# Dogfish3D_-_MCU_-_ATSAMD21G18.net
KiCad netlist of a schematic drawn in Altium Designer
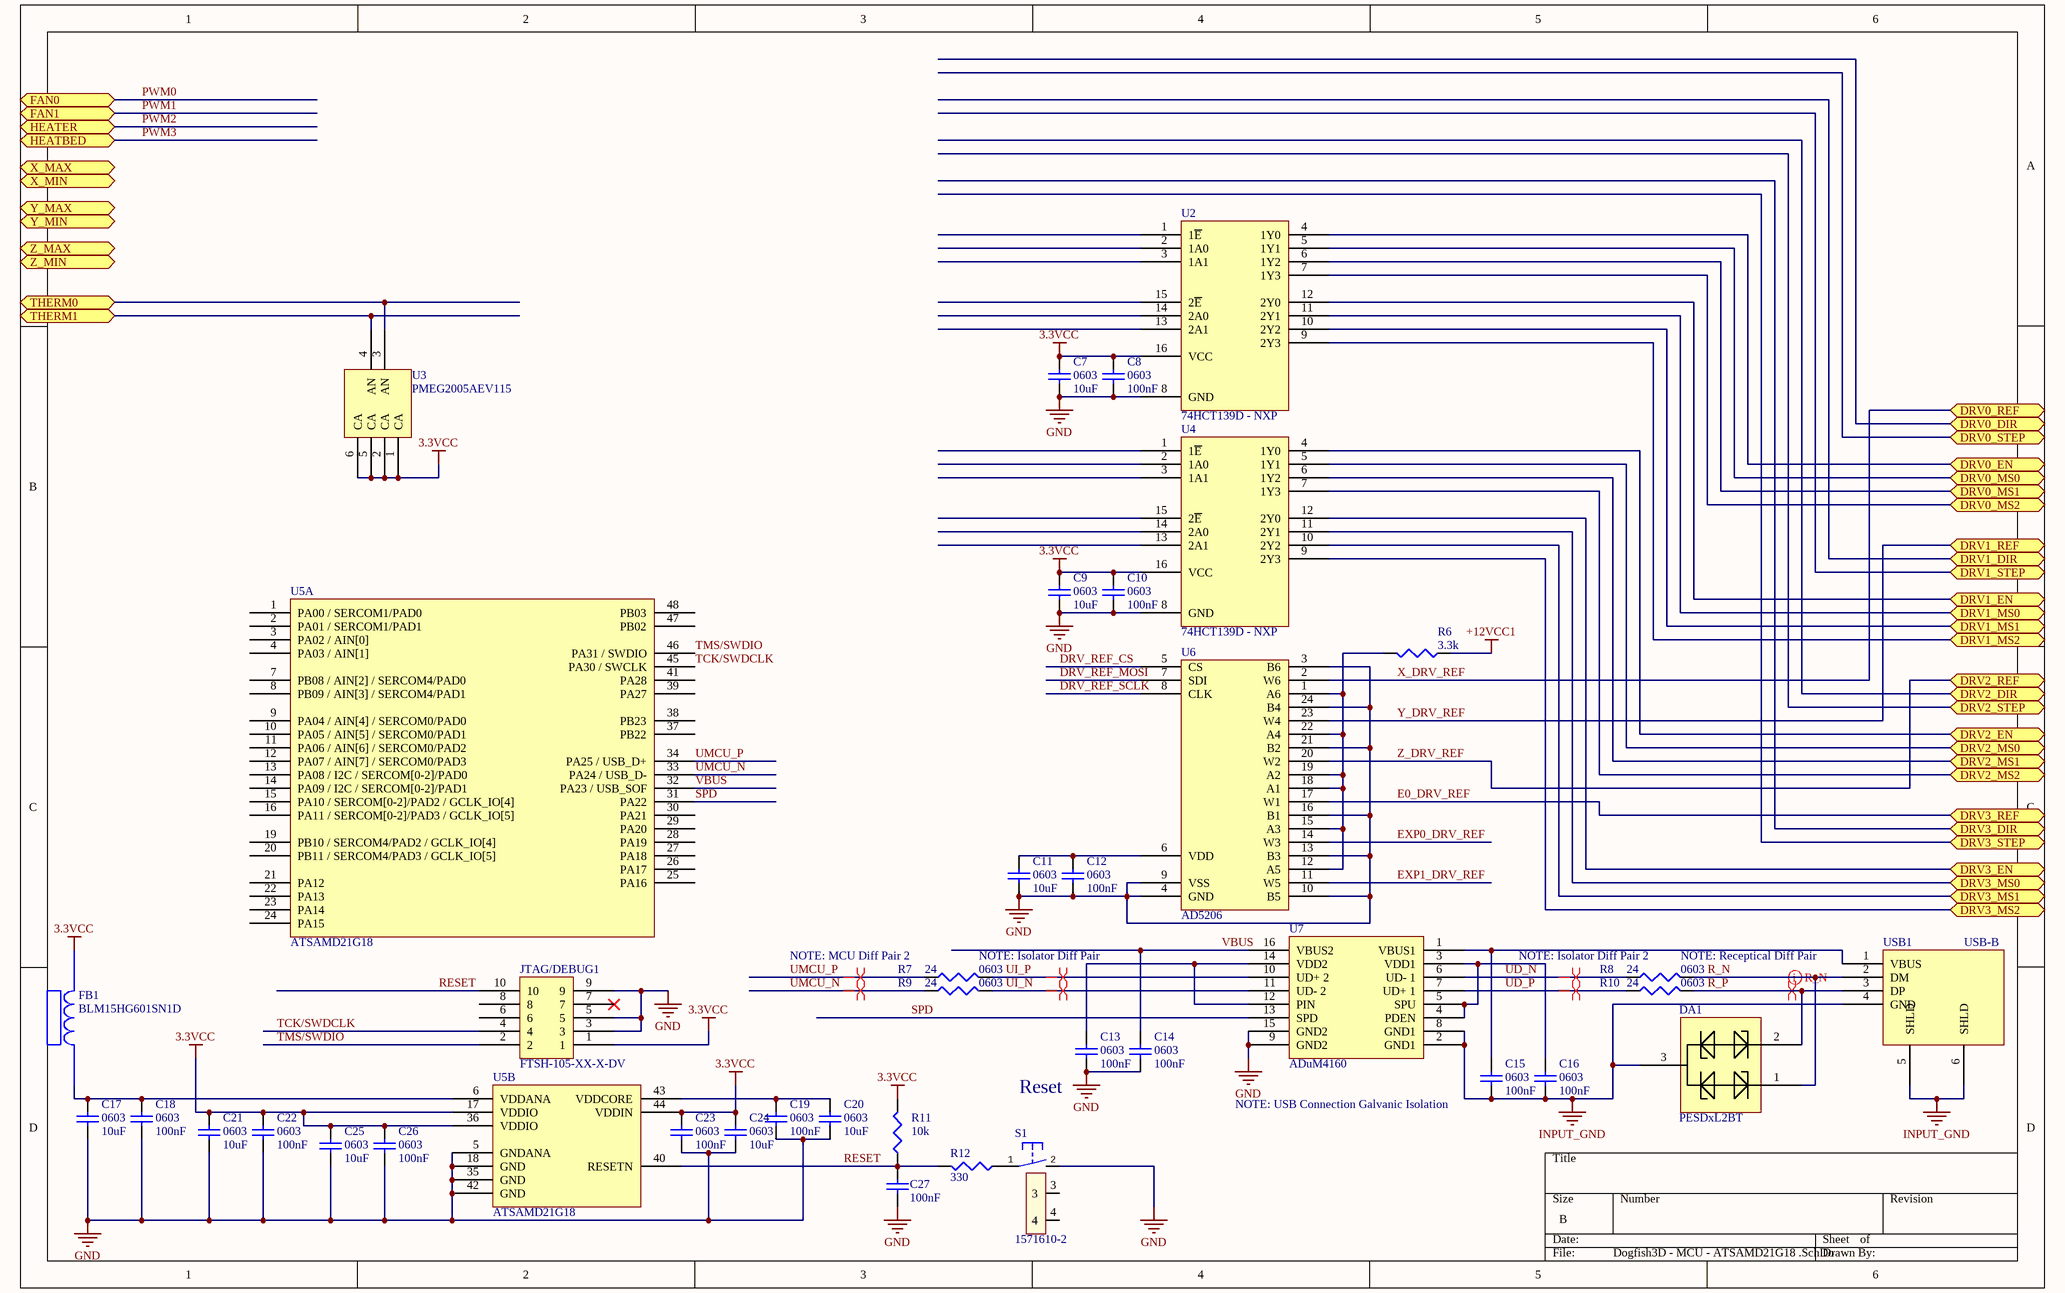
[diagram p0: Dogfish3D - MCU - ATSAMD21G18 .SchDoc]

(export (version "E")
  (design (tool "Eeschema 10.0.6"))
  (components
    (comp (ref "C7")
      (value "0603")
      (footprint "1608[0603]")
      (description "Capacitor (Semiconductor SIM Model)")
      (fields (field (name "ALTIUM_VALUE") "10uF") (field (name "PUBLISHER") "Altium Limited"))
      (libsource (lib "Miscellaneous Devices") (part "Cap Semi"))
    )
    (comp (ref "C8")
      (value "0603")
      (footprint "1608[0603]")
      (description "Capacitor (Semiconductor SIM Model)")
      (fields (field (name "ALTIUM_VALUE") "100nF") (field (name "PUBLISHER") "Altium Limited"))
      (libsource (lib "Miscellaneous Devices") (part "Cap Semi"))
    )
    (comp (ref "C9")
      (value "0603")
      (footprint "1608[0603]")
      (description "Capacitor (Semiconductor SIM Model)")
      (fields (field (name "ALTIUM_VALUE") "10uF") (field (name "PUBLISHER") "Altium Limited"))
      (libsource (lib "Miscellaneous Devices") (part "Cap Semi"))
    )
    (comp (ref "C10")
      (value "0603")
      (footprint "1608[0603]")
      (description "Capacitor (Semiconductor SIM Model)")
      (fields (field (name "ALTIUM_VALUE") "100nF") (field (name "PUBLISHER") "Altium Limited"))
      (libsource (lib "Miscellaneous Devices") (part "Cap Semi"))
    )
    (comp (ref "C11")
      (value "0603")
      (footprint "1608[0603]")
      (description "Capacitor (Semiconductor SIM Model)")
      (fields (field (name "ALTIUM_VALUE") "10uF") (field (name "PUBLISHER") "Altium Limited"))
      (libsource (lib "Miscellaneous Devices") (part "Cap Semi"))
    )
    (comp (ref "C12")
      (value "0603")
      (footprint "1608[0603]")
      (description "Capacitor (Semiconductor SIM Model)")
      (fields (field (name "ALTIUM_VALUE") "100nF") (field (name "PUBLISHER") "Altium Limited"))
      (libsource (lib "Miscellaneous Devices") (part "Cap Semi"))
    )
    (comp (ref "C13")
      (value "0603")
      (footprint "1608[0603]")
      (description "Capacitor (Semiconductor SIM Model)")
      (fields (field (name "ALTIUM_VALUE") "100nF") (field (name "PUBLISHER") "Altium Limited"))
      (libsource (lib "Miscellaneous Devices") (part "Cap Semi"))
    )
    (comp (ref "C14")
      (value "0603")
      (footprint "1608[0603]")
      (description "Capacitor (Semiconductor SIM Model)")
      (fields (field (name "ALTIUM_VALUE") "100nF") (field (name "PUBLISHER") "Altium Limited"))
      (libsource (lib "Miscellaneous Devices") (part "Cap Semi"))
    )
    (comp (ref "C15")
      (value "0603")
      (footprint "1608[0603]")
      (description "Capacitor (Semiconductor SIM Model)")
      (fields (field (name "ALTIUM_VALUE") "100nF") (field (name "PUBLISHER") "Altium Limited"))
      (libsource (lib "Miscellaneous Devices") (part "Cap Semi"))
    )
    (comp (ref "C16")
      (value "0603")
      (footprint "1608[0603]")
      (description "Capacitor (Semiconductor SIM Model)")
      (fields (field (name "ALTIUM_VALUE") "100nF") (field (name "PUBLISHER") "Altium Limited"))
      (libsource (lib "Miscellaneous Devices") (part "Cap Semi"))
    )
    (comp (ref "C17")
      (value "0603")
      (footprint "1608[0603]")
      (description "Capacitor (Semiconductor SIM Model)")
      (fields (field (name "ALTIUM_VALUE") "10uF") (field (name "PUBLISHER") "Altium Limited"))
      (libsource (lib "Miscellaneous Devices") (part "Cap Semi"))
    )
    (comp (ref "C18")
      (value "0603")
      (footprint "1608[0603]")
      (description "Capacitor (Semiconductor SIM Model)")
      (fields (field (name "ALTIUM_VALUE") "100nF") (field (name "PUBLISHER") "Altium Limited"))
      (libsource (lib "Miscellaneous Devices") (part "Cap Semi"))
    )
    (comp (ref "C19")
      (value "0603")
      (footprint "1608[0603]")
      (description "Capacitor (Semiconductor SIM Model)")
      (fields (field (name "ALTIUM_VALUE") "100nF") (field (name "PUBLISHER") "Altium Limited"))
      (libsource (lib "Miscellaneous Devices") (part "Cap Semi"))
    )
    (comp (ref "C20")
      (value "0603")
      (footprint "1608[0603]")
      (description "Capacitor (Semiconductor SIM Model)")
      (fields (field (name "ALTIUM_VALUE") "10uF") (field (name "PUBLISHER") "Altium Limited"))
      (libsource (lib "Miscellaneous Devices") (part "Cap Semi"))
    )
    (comp (ref "C21")
      (value "0603")
      (footprint "1608[0603]")
      (description "Capacitor (Semiconductor SIM Model)")
      (fields (field (name "ALTIUM_VALUE") "10uF") (field (name "PUBLISHER") "Altium Limited"))
      (libsource (lib "Miscellaneous Devices") (part "Cap Semi"))
    )
    (comp (ref "C22")
      (value "0603")
      (footprint "1608[0603]")
      (description "Capacitor (Semiconductor SIM Model)")
      (fields (field (name "ALTIUM_VALUE") "100nF") (field (name "PUBLISHER") "Altium Limited"))
      (libsource (lib "Miscellaneous Devices") (part "Cap Semi"))
    )
    (comp (ref "C23")
      (value "0603")
      (footprint "1608[0603]")
      (description "Capacitor (Semiconductor SIM Model)")
      (fields (field (name "ALTIUM_VALUE") "100nF") (field (name "PUBLISHER") "Altium Limited"))
      (libsource (lib "Miscellaneous Devices") (part "Cap Semi"))
    )
    (comp (ref "C24")
      (value "0603")
      (footprint "1608[0603]")
      (description "Capacitor (Semiconductor SIM Model)")
      (fields (field (name "ALTIUM_VALUE") "10uF") (field (name "PUBLISHER") "Altium Limited"))
      (libsource (lib "Miscellaneous Devices") (part "Cap Semi"))
    )
    (comp (ref "C25")
      (value "0603")
      (footprint "1608[0603]")
      (description "Capacitor (Semiconductor SIM Model)")
      (fields (field (name "ALTIUM_VALUE") "10uF") (field (name "PUBLISHER") "Altium Limited"))
      (libsource (lib "Miscellaneous Devices") (part "Cap Semi"))
    )
    (comp (ref "C26")
      (value "0603")
      (footprint "1608[0603]")
      (description "Capacitor (Semiconductor SIM Model)")
      (fields (field (name "ALTIUM_VALUE") "100nF") (field (name "PUBLISHER") "Altium Limited"))
      (libsource (lib "Miscellaneous Devices") (part "Cap Semi"))
    )
    (comp (ref "C27")
      (value "100nF")
      (footprint "1608[0603]")
      (description "Capacitor (Semiconductor SIM Model)")
      (fields (field (name "Comment") "Cap Semi") (field (name "PUBLISHER") "Altium Limited"))
      (libsource (lib "Miscellaneous Devices") (part "Cap Semi"))
    )
    (comp (ref "DA1")
      (value "PESDxL2BT")
      (footprint "SOT95P230X110-3N")
      (description "PESDxL2BT TVS Diode Array 2x")
      (libsource (lib "ZMBo Schematic Library") (part "PESDxL2BT"))
    )
    (comp (ref "FB1")
      (value "BLM15HG601SN1D")
      (footprint "BLM18PG121SN1D")
      (libsource (lib "AHD Part Library") (part "BLM15HG601SN1D"))
    )
    (comp (ref "JTAG/DEBUG1")
      (value "FTSH-105-XX-X-DV")
      (footprint "FTSH-105-XX-X-DV")
      (libsource (lib "Adams Altium Library") (part "ARM Cortex JTAG-DEBUG Header"))
    )
    (comp (ref "R6")
      (value "3.3k")
      (footprint "J1-0603")
      (description "Resistor")
      (fields (field (name "Comment") "Res3") (field (name "PUBLISHER") "Altium Limited"))
      (libsource (lib "Miscellaneous Devices") (part "Res3"))
    )
    (comp (ref "R7")
      (value "0603")
      (footprint "J1-0603")
      (description "Resistor")
      (fields (field (name "ALTIUM_VALUE") "24") (field (name "PUBLISHER") "Altium Limited"))
      (libsource (lib "Miscellaneous Devices") (part "Res3"))
    )
    (comp (ref "R8")
      (value "0603")
      (footprint "J1-0603")
      (description "Resistor")
      (fields (field (name "ALTIUM_VALUE") "24") (field (name "PUBLISHER") "Altium Limited"))
      (libsource (lib "Miscellaneous Devices") (part "Res3"))
    )
    (comp (ref "R9")
      (value "0603")
      (footprint "J1-0603")
      (description "Resistor")
      (fields (field (name "ALTIUM_VALUE") "24") (field (name "PUBLISHER") "Altium Limited"))
      (libsource (lib "Miscellaneous Devices") (part "Res3"))
    )
    (comp (ref "R10")
      (value "0603")
      (footprint "J1-0603")
      (description "Resistor")
      (fields (field (name "ALTIUM_VALUE") "24") (field (name "PUBLISHER") "Altium Limited"))
      (libsource (lib "Miscellaneous Devices") (part "Res3"))
    )
    (comp (ref "R11")
      (value "10k")
      (footprint "J1-0603")
      (description "Resistor")
      (fields (field (name "Comment") "Res3") (field (name "PUBLISHER") "Altium Limited"))
      (libsource (lib "Miscellaneous Devices") (part "Res3"))
    )
    (comp (ref "R12")
      (value "330")
      (footprint "J1-0603")
      (description "Resistor")
      (fields (field (name "Comment") "Res3") (field (name "PUBLISHER") "Altium Limited"))
      (libsource (lib "Miscellaneous Devices") (part "Res3"))
    )
    (comp (ref "S1")
      (value "1571610-2")
      (footprint "B3F-31XX")
      (description "SWTCH Momentary Washable")
      (fields
        (field (name "MANUFACTURER") "Omron")
        (field (name "MANUFACTURER_1") "TE")
        (field (name "PUBLISHER") "UltiMachine")
      )
      (libsource (lib "ZMBo Schematic Library") (part "1571610-2_1"))
    )
    (comp (ref "U2")
      (value "74HCT139D - NXP")
      (footprint "SOIC127P600X175-16N")
      (description "74HCT139D 2-4 dual Decoder from NXP")
      (libsource (lib "Dogfish3D") (part "74HCT139D - NXP"))
    )
    (comp (ref "U3")
      (value "PMEG2005AEV115")
      (footprint "PMEG2005AEV115")
      (libsource (lib "Adams Altium Library") (part "PMEG2005AEV115"))
    )
    (comp (ref "U4")
      (value "74HCT139D - NXP")
      (footprint "SOIC127P600X175-16N")
      (description "74HCT139D 2-4 dual Decoder from NXP")
      (libsource (lib "Dogfish3D") (part "74HCT139D - NXP"))
    )
    (comp (ref "U5")
      (value "ATSAMD21G18")
      (footprint "TSQFP50P900X900X120-48N")
      (libsource (lib "Dogfish3D") (part "ATSAMD21G18"))
    )
    (comp (ref "U6")
      (value "AD5206")
      (footprint "AD5206 & AD5204")
      (libsource (lib "ZMBo Schematic Library") (part "AD5206"))
    )
    (comp (ref "U7")
      (value "ADuM4160")
      (footprint "ADuM4160")
      (description "USB Opto Isolator")
      (libsource (lib "ZMBo Schematic Library") (part "ADuM4160"))
    )
    (comp (ref "USB1")
      (value "USB-B")
      (footprint "PN61729")
      (libsource (lib "ZMBo Schematic Library") (part "USB-B"))
    )
  )
  (nets
    (net (code "1") (name "+12VCC1") (class "Default")
      (node (ref "R6") (pin "1") (pinfunction "1_1") (pintype "passive"))
    )
    (net (code "3") (name "/DRV0_EN") (class "Default")
      (node (ref "U2") (pin "4") (pinfunction "1Y0_4") (pintype "passive"))
    )
    (net (code "4") (name "/DRV0_MS0") (class "Default")
      (node (ref "U2") (pin "5") (pinfunction "1Y1_5") (pintype "passive"))
    )
    (net (code "5") (name "/DRV0_MS1") (class "Default")
      (node (ref "U2") (pin "6") (pinfunction "1Y2_6") (pintype "passive"))
    )
    (net (code "6") (name "/DRV0_MS2") (class "Default")
      (node (ref "U2") (pin "7") (pinfunction "1Y3_7") (pintype "passive"))
    )
    (net (code "9") (name "/DRV1_EN") (class "Default")
      (node (ref "U2") (pin "12") (pinfunction "2Y0_12") (pintype "passive"))
    )
    (net (code "10") (name "/DRV1_MS0") (class "Default")
      (node (ref "U2") (pin "11") (pinfunction "2Y1_11") (pintype "passive"))
    )
    (net (code "11") (name "/DRV1_MS1") (class "Default")
      (node (ref "U2") (pin "10") (pinfunction "2Y2_10") (pintype "passive"))
    )
    (net (code "12") (name "/DRV1_MS2") (class "Default")
      (node (ref "U2") (pin "9") (pinfunction "2Y3_9") (pintype "passive"))
    )
    (net (code "15") (name "/DRV2_EN") (class "Default")
      (node (ref "U4") (pin "4") (pinfunction "1Y0_4") (pintype "passive"))
    )
    (net (code "16") (name "/DRV2_MS0") (class "Default")
      (node (ref "U4") (pin "5") (pinfunction "1Y1_5") (pintype "passive"))
    )
    (net (code "17") (name "/DRV2_MS1") (class "Default")
      (node (ref "U4") (pin "6") (pinfunction "1Y2_6") (pintype "passive"))
    )
    (net (code "18") (name "/DRV2_MS2") (class "Default")
      (node (ref "U4") (pin "7") (pinfunction "1Y3_7") (pintype "passive"))
    )
    (net (code "21") (name "/DRV3_EN") (class "Default")
      (node (ref "U4") (pin "12") (pinfunction "2Y0_12") (pintype "passive"))
    )
    (net (code "22") (name "/DRV3_MS0") (class "Default")
      (node (ref "U4") (pin "11") (pinfunction "2Y1_11") (pintype "passive"))
    )
    (net (code "23") (name "/DRV3_MS1") (class "Default")
      (node (ref "U4") (pin "10") (pinfunction "2Y2_10") (pintype "passive"))
    )
    (net (code "24") (name "/DRV3_MS2") (class "Default")
      (node (ref "U4") (pin "9") (pinfunction "2Y3_9") (pintype "passive"))
    )
    (net (code "26") (name "/DRV_REF_CS") (class "Default")
      (node (ref "U6") (pin "5") (pinfunction "CS_5") (pintype "passive"))
    )
    (net (code "27") (name "/DRV_REF_MOSI") (class "Default")
      (node (ref "U6") (pin "7") (pinfunction "SDI_7") (pintype "passive"))
    )
    (net (code "28") (name "/DRV_REF_SCLK") (class "Default")
      (node (ref "U6") (pin "8") (pinfunction "CLK_8") (pintype "passive"))
    )
    (net (code "29") (name "/E0_DRV_REF") (class "Default")
      (node (ref "U6") (pin "17") (pinfunction "W1_17") (pintype "passive"))
    )
    (net (code "30") (name "/EXP0_DRV_REF") (class "Default")
      (node (ref "U6") (pin "14") (pinfunction "W3_14") (pintype "passive"))
    )
    (net (code "31") (name "/EXP1_DRV_REF") (class "Default")
      (node (ref "U6") (pin "11") (pinfunction "W5_11") (pintype "passive"))
    )
    (net (code "36") (name "/RESET") (class "Default")
      (node (ref "C27") (pin "2") (pinfunction "2_2") (pintype "passive"))
      (node (ref "JTAG/DEBUG1") (pin "10") (pinfunction "10_10") (pintype "passive"))
      (node (ref "R11") (pin "1") (pinfunction "1_1") (pintype "passive"))
      (node (ref "R12") (pin "2") (pinfunction "2_2") (pintype "passive"))
      (node (ref "U5") (pin "40") (pinfunction "RESETN_40") (pintype "passive"))
    )
    (net (code "37") (name "/R_N") (class "Default")
      (node (ref "DA1") (pin "1") (pinfunction "1_1") (pintype "passive"))
      (node (ref "R8") (pin "2") (pinfunction "2_2") (pintype "passive"))
      (node (ref "USB1") (pin "2") (pinfunction "DM_2") (pintype "passive"))
    )
    (net (code "38") (name "/R_P") (class "Default")
      (node (ref "DA1") (pin "2") (pinfunction "2_2") (pintype "passive"))
      (node (ref "R10") (pin "2") (pinfunction "2_2") (pintype "passive"))
      (node (ref "USB1") (pin "3") (pinfunction "DP_3") (pintype "passive"))
    )
    (net (code "39") (name "/SPD") (class "Default")
      (node (ref "U5") (pin "31") (pinfunction "PA22_31") (pintype "passive"))
      (node (ref "U7") (pin "13") (pinfunction "SPD_13") (pintype "passive"))
    )
    (net (code "40") (name "/TCK{slash}SWDCLK") (class "Default")
      (node (ref "JTAG/DEBUG1") (pin "4") (pinfunction "4_4") (pintype "passive"))
      (node (ref "U5") (pin "45") (pinfunction "PA30_/_SWCLK_45") (pintype "passive"))
    )
    (net (code "41") (name "/THERM0") (class "Default")
      (node (ref "U3") (pin "3") (pinfunction "AN_3") (pintype "passive"))
    )
    (net (code "42") (name "/THERM1") (class "Default")
      (node (ref "U3") (pin "4") (pinfunction "AN_4") (pintype "passive"))
    )
    (net (code "43") (name "/TMS{slash}SWDIO") (class "Default")
      (node (ref "JTAG/DEBUG1") (pin "2") (pinfunction "2_2") (pintype "passive"))
      (node (ref "U5") (pin "46") (pinfunction "PA31_/_SWDIO_46") (pintype "passive"))
    )
    (net (code "44") (name "/UD_N") (class "Default")
      (node (ref "R8") (pin "1") (pinfunction "1_1") (pintype "passive"))
      (node (ref "U7") (pin "6") (pinfunction "UD-_1_6") (pintype "passive"))
    )
    (net (code "45") (name "/UD_P") (class "Default")
      (node (ref "R10") (pin "1") (pinfunction "1_1") (pintype "passive"))
      (node (ref "U7") (pin "7") (pinfunction "UD+_1_7") (pintype "passive"))
    )
    (net (code "46") (name "/UI_N") (class "Default")
      (node (ref "R9") (pin "2") (pinfunction "2_2") (pintype "passive"))
      (node (ref "U7") (pin "11") (pinfunction "UD-_2_11") (pintype "passive"))
    )
    (net (code "47") (name "/UI_P") (class "Default")
      (node (ref "R7") (pin "2") (pinfunction "2_2") (pintype "passive"))
      (node (ref "U7") (pin "10") (pinfunction "UD+_2_10") (pintype "passive"))
    )
    (net (code "48") (name "/UMCU_N") (class "Default")
      (node (ref "R9") (pin "1") (pinfunction "1_1") (pintype "passive"))
      (node (ref "U5") (pin "33") (pinfunction "PA24_/_USB_D-_33") (pintype "passive"))
    )
    (net (code "49") (name "/UMCU_P") (class "Default")
      (node (ref "R7") (pin "1") (pinfunction "1_1") (pintype "passive"))
      (node (ref "U5") (pin "34") (pinfunction "PA25_/_USB_D+_34") (pintype "passive"))
    )
    (net (code "50") (name "/VBUS") (class "Default")
      (node (ref "C14") (pin "2") (pinfunction "2_2") (pintype "passive"))
      (node (ref "U5") (pin "32") (pinfunction "PA23_/_USB_SOF_32") (pintype "passive"))
      (node (ref "U7") (pin "16") (pinfunction "VBUS2_16") (pintype "passive"))
    )
    (net (code "51") (name "/X_DRV_REF") (class "Default")
      (node (ref "U6") (pin "2") (pinfunction "W6_2") (pintype "passive"))
    )
    (net (code "54") (name "/Y_DRV_REF") (class "Default")
      (node (ref "U6") (pin "23") (pinfunction "W4_23") (pintype "passive"))
    )
    (net (code "57") (name "/Z_DRV_REF") (class "Default")
      (node (ref "U6") (pin "20") (pinfunction "W2_20") (pintype "passive"))
    )
    (net (code "60") (name "3.3VCC") (class "Default")
      (node (ref "C10") (pin "2") (pinfunction "2_2") (pintype "passive"))
      (node (ref "C21") (pin "2") (pinfunction "2_2") (pintype "passive"))
      (node (ref "C22") (pin "2") (pinfunction "2_2") (pintype "passive"))
      (node (ref "C23") (pin "2") (pinfunction "2_2") (pintype "passive"))
      (node (ref "C24") (pin "2") (pinfunction "2_2") (pintype "passive"))
      (node (ref "C25") (pin "2") (pinfunction "2_2") (pintype "passive"))
      (node (ref "C26") (pin "2") (pinfunction "2_2") (pintype "passive"))
      (node (ref "C7") (pin "2") (pinfunction "2_2") (pintype "passive"))
      (node (ref "C8") (pin "2") (pinfunction "2_2") (pintype "passive"))
      (node (ref "C9") (pin "2") (pinfunction "2_2") (pintype "passive"))
      (node (ref "FB1") (pin "2") (pinfunction "2_2") (pintype "passive"))
      (node (ref "JTAG/DEBUG1") (pin "1") (pinfunction "1_1") (pintype "passive"))
      (node (ref "R11") (pin "2") (pinfunction "2_2") (pintype "passive"))
      (node (ref "U2") (pin "16") (pinfunction "VCC_16") (pintype "passive"))
      (node (ref "U3") (pin "1") (pinfunction "CA_1") (pintype "passive"))
      (node (ref "U3") (pin "2") (pinfunction "CA_2") (pintype "passive"))
      (node (ref "U3") (pin "5") (pinfunction "CA_5") (pintype "passive"))
      (node (ref "U3") (pin "6") (pinfunction "CA_6") (pintype "passive"))
      (node (ref "U4") (pin "16") (pinfunction "VCC_16") (pintype "passive"))
      (node (ref "U5") (pin "17") (pinfunction "VDDIO_17") (pintype "passive"))
      (node (ref "U5") (pin "36") (pinfunction "VDDIO_36") (pintype "passive"))
      (node (ref "U5") (pin "44") (pinfunction "VDDIN_44") (pintype "passive"))
    )
    (net (code "61") (name "GND") (class "Default")
      (node (ref "C10") (pin "1") (pinfunction "1_1") (pintype "passive"))
      (node (ref "C11") (pin "1") (pinfunction "1_1") (pintype "passive"))
      (node (ref "C12") (pin "1") (pinfunction "1_1") (pintype "passive"))
      (node (ref "C13") (pin "1") (pinfunction "1_1") (pintype "passive"))
      (node (ref "C14") (pin "1") (pinfunction "1_1") (pintype "passive"))
      (node (ref "C17") (pin "1") (pinfunction "1_1") (pintype "passive"))
      (node (ref "C18") (pin "1") (pinfunction "1_1") (pintype "passive"))
      (node (ref "C19") (pin "1") (pinfunction "1_1") (pintype "passive"))
      (node (ref "C20") (pin "1") (pinfunction "1_1") (pintype "passive"))
      (node (ref "C21") (pin "1") (pinfunction "1_1") (pintype "passive"))
      (node (ref "C22") (pin "1") (pinfunction "1_1") (pintype "passive"))
      (node (ref "C23") (pin "1") (pinfunction "1_1") (pintype "passive"))
      (node (ref "C24") (pin "1") (pinfunction "1_1") (pintype "passive"))
      (node (ref "C25") (pin "1") (pinfunction "1_1") (pintype "passive"))
      (node (ref "C26") (pin "1") (pinfunction "1_1") (pintype "passive"))
      (node (ref "C27") (pin "1") (pinfunction "1_1") (pintype "passive"))
      (node (ref "C7") (pin "1") (pinfunction "1_1") (pintype "passive"))
      (node (ref "C8") (pin "1") (pinfunction "1_1") (pintype "passive"))
      (node (ref "C9") (pin "1") (pinfunction "1_1") (pintype "passive"))
      (node (ref "JTAG/DEBUG1") (pin "3") (pinfunction "3_3") (pintype "passive"))
      (node (ref "JTAG/DEBUG1") (pin "5") (pinfunction "5_5") (pintype "passive"))
      (node (ref "JTAG/DEBUG1") (pin "9") (pinfunction "9_9") (pintype "passive"))
      (node (ref "S1") (pin "2") (pinfunction "S_2") (pintype "passive"))
      (node (ref "U2") (pin "8") (pinfunction "GND_8") (pintype "passive"))
      (node (ref "U4") (pin "8") (pinfunction "GND_8") (pintype "passive"))
      (node (ref "U5") (pin "18") (pinfunction "GND_18") (pintype "passive"))
      (node (ref "U5") (pin "35") (pinfunction "GND_35") (pintype "passive"))
      (node (ref "U5") (pin "42") (pinfunction "GND_42") (pintype "passive"))
      (node (ref "U5") (pin "5") (pinfunction "GNDANA_5") (pintype "passive"))
      (node (ref "U6") (pin "10") (pinfunction "B5_10") (pintype "passive"))
      (node (ref "U6") (pin "13") (pinfunction "B3_13") (pintype "passive"))
      (node (ref "U6") (pin "16") (pinfunction "B1_16") (pintype "passive"))
      (node (ref "U6") (pin "21") (pinfunction "B2_21") (pintype "passive"))
      (node (ref "U6") (pin "24") (pinfunction "B4_24") (pintype "passive"))
      (node (ref "U6") (pin "3") (pinfunction "B6_3") (pintype "passive"))
      (node (ref "U6") (pin "4") (pinfunction "GND_4") (pintype "passive"))
      (node (ref "U6") (pin "9") (pinfunction "VSS_9") (pintype "passive"))
      (node (ref "U7") (pin "15") (pinfunction "GND2_15") (pintype "passive"))
      (node (ref "U7") (pin "9") (pinfunction "GND2_9") (pintype "passive"))
    )
    (net (code "62") (name "INPUT_GND") (class "Default")
      (node (ref "C15") (pin "1") (pinfunction "1_1") (pintype "passive"))
      (node (ref "C16") (pin "1") (pinfunction "1_1") (pintype "passive"))
      (node (ref "DA1") (pin "3") (pinfunction "3_3") (pintype "passive"))
      (node (ref "U7") (pin "2") (pinfunction "GND1_2") (pintype "passive"))
      (node (ref "U7") (pin "8") (pinfunction "GND1_8") (pintype "passive"))
      (node (ref "USB1") (pin "4") (pinfunction "GND_4") (pintype "passive"))
      (node (ref "USB1") (pin "5") (pinfunction "SHLD_5") (pintype "passive"))
      (node (ref "USB1") (pin "6") (pinfunction "SHLD_6") (pintype "passive"))
    )
    (net (code "63") (name "Net-(S1-P)") (class "Default")
      (node (ref "R12") (pin "1") (pinfunction "1_1") (pintype "passive"))
      (node (ref "S1") (pin "1") (pinfunction "P_1") (pintype "passive"))
    )
    (net (code "64") (name "Net-(U5B-VDDANA)") (class "Default")
      (node (ref "C17") (pin "2") (pinfunction "2_2") (pintype "passive"))
      (node (ref "C18") (pin "2") (pinfunction "2_2") (pintype "passive"))
      (node (ref "FB1") (pin "1") (pinfunction "1_1") (pintype "passive"))
      (node (ref "U5") (pin "6") (pinfunction "VDDANA_6") (pintype "passive"))
    )
    (net (code "65") (name "Net-(U5B-VDDCORE)") (class "Default")
      (node (ref "C19") (pin "2") (pinfunction "2_2") (pintype "passive"))
      (node (ref "C20") (pin "2") (pinfunction "2_2") (pintype "passive"))
      (node (ref "U5") (pin "43") (pinfunction "VDDCORE_43") (pintype "passive"))
    )
    (net (code "66") (name "Net-(U6-A1)") (class "Default")
      (node (ref "R6") (pin "2") (pinfunction "2_2") (pintype "passive"))
      (node (ref "U6") (pin "1") (pinfunction "A6_1") (pintype "passive"))
      (node (ref "U6") (pin "12") (pinfunction "A5_12") (pintype "passive"))
      (node (ref "U6") (pin "15") (pinfunction "A3_15") (pintype "passive"))
      (node (ref "U6") (pin "18") (pinfunction "A1_18") (pintype "passive"))
      (node (ref "U6") (pin "19") (pinfunction "A2_19") (pintype "passive"))
      (node (ref "U6") (pin "22") (pinfunction "A4_22") (pintype "passive"))
    )
    (net (code "67") (name "Net-(U6-VDD)") (class "Default")
      (node (ref "C11") (pin "2") (pinfunction "2_2") (pintype "passive"))
      (node (ref "C12") (pin "2") (pinfunction "2_2") (pintype "passive"))
      (node (ref "U6") (pin "6") (pinfunction "VDD_6") (pintype "passive"))
    )
    (net (code "68") (name "Net-(U7-PDEN)") (class "Default")
      (node (ref "C16") (pin "2") (pinfunction "2_2") (pintype "passive"))
      (node (ref "U7") (pin "3") (pinfunction "VDD1_3") (pintype "passive"))
      (node (ref "U7") (pin "4") (pinfunction "PDEN_4") (pintype "passive"))
      (node (ref "U7") (pin "5") (pinfunction "SPU_5") (pintype "passive"))
    )
    (net (code "69") (name "Net-(U7-PIN)") (class "Default")
      (node (ref "C13") (pin "2") (pinfunction "2_2") (pintype "passive"))
      (node (ref "U7") (pin "12") (pinfunction "PIN_12") (pintype "passive"))
      (node (ref "U7") (pin "14") (pinfunction "VDD2_14") (pintype "passive"))
    )
    (net (code "70") (name "Net-(U7-VBUS1)") (class "Default")
      (node (ref "C15") (pin "2") (pinfunction "2_2") (pintype "passive"))
      (node (ref "U7") (pin "1") (pinfunction "VBUS1_1") (pintype "passive"))
      (node (ref "USB1") (pin "1") (pinfunction "VBUS_1") (pintype "passive"))
    )
    (net (code "71") (name "unconnected-(JTAG/DEBUG1-Pad6)") (class "Default")
      (node (ref "JTAG/DEBUG1") (pin "6") (pinfunction "6_6") (pintype "passive"))
    )
    (net (code "72") (name "unconnected-(JTAG/DEBUG1-Pad7)") (class "Default")
      (node (ref "JTAG/DEBUG1") (pin "7") (pinfunction "7_7") (pintype "passive+no_connect"))
    )
    (net (code "73") (name "unconnected-(JTAG/DEBUG1-Pad8)") (class "Default")
      (node (ref "JTAG/DEBUG1") (pin "8") (pinfunction "8_8") (pintype "passive"))
    )
    (net (code "74") (name "unconnected-(S1-Pad3)") (class "Default")
      (node (ref "S1") (pin "3") (pinfunction "3_3") (pintype "power_in"))
    )
    (net (code "75") (name "unconnected-(S1-Pad4)") (class "Default")
      (node (ref "S1") (pin "4") (pinfunction "4_4") (pintype "power_in"))
    )
    (net (code "76") (name "unconnected-(U2-1A0-Pad2)") (class "Default")
      (node (ref "U2") (pin "2") (pinfunction "1A0_2") (pintype "passive"))
    )
    (net (code "77") (name "unconnected-(U2-1A1-Pad3)") (class "Default")
      (node (ref "U2") (pin "3") (pinfunction "1A1_3") (pintype "passive"))
    )
    (net (code "78") (name "unconnected-(U2-1~{E}-Pad1)") (class "Default")
      (node (ref "U2") (pin "1") (pinfunction "1~{E}_1") (pintype "passive"))
    )
    (net (code "79") (name "unconnected-(U2-2A0-Pad14)") (class "Default")
      (node (ref "U2") (pin "14") (pinfunction "2A0_14") (pintype "passive"))
    )
    (net (code "80") (name "unconnected-(U2-2A1-Pad13)") (class "Default")
      (node (ref "U2") (pin "13") (pinfunction "2A1_13") (pintype "passive"))
    )
    (net (code "81") (name "unconnected-(U2-2~{E}-Pad15)") (class "Default")
      (node (ref "U2") (pin "15") (pinfunction "2~{E}_15") (pintype "passive"))
    )
    (net (code "82") (name "unconnected-(U4-1A0-Pad2)") (class "Default")
      (node (ref "U4") (pin "2") (pinfunction "1A0_2") (pintype "passive"))
    )
    (net (code "83") (name "unconnected-(U4-1A1-Pad3)") (class "Default")
      (node (ref "U4") (pin "3") (pinfunction "1A1_3") (pintype "passive"))
    )
    (net (code "84") (name "unconnected-(U4-1~{E}-Pad1)") (class "Default")
      (node (ref "U4") (pin "1") (pinfunction "1~{E}_1") (pintype "passive"))
    )
    (net (code "85") (name "unconnected-(U4-2A0-Pad14)") (class "Default")
      (node (ref "U4") (pin "14") (pinfunction "2A0_14") (pintype "passive"))
    )
    (net (code "86") (name "unconnected-(U4-2A1-Pad13)") (class "Default")
      (node (ref "U4") (pin "13") (pinfunction "2A1_13") (pintype "passive"))
    )
    (net (code "87") (name "unconnected-(U4-2~{E}-Pad15)") (class "Default")
      (node (ref "U4") (pin "15") (pinfunction "2~{E}_15") (pintype "passive"))
    )
    (net (code "88") (name "unconnected-(U5A-PA00_{slash}_SERCOM1{slash}PAD0-Pad1)") (class "Default")
      (node (ref "U5") (pin "1") (pinfunction "PA00_/_SERCOM1/PAD0_1") (pintype "passive"))
    )
    (net (code "89") (name "unconnected-(U5A-PA01_{slash}_SERCOM1{slash}PAD1-Pad2)") (class "Default")
      (node (ref "U5") (pin "2") (pinfunction "PA01_/_SERCOM1/PAD1_2") (pintype "passive"))
    )
    (net (code "90") (name "unconnected-(U5A-PA02_{slash}_AIN[0]-Pad3)") (class "Default")
      (node (ref "U5") (pin "3") (pinfunction "PA02_/_AIN[0]_3") (pintype "passive"))
    )
    (net (code "91") (name "unconnected-(U5A-PA03_{slash}_AIN[1]-Pad4)") (class "Default")
      (node (ref "U5") (pin "4") (pinfunction "PA03_/_AIN[1]_4") (pintype "passive"))
    )
    (net (code "92") (name "unconnected-(U5A-PA04_{slash}_AIN[4]_{slash}_SERCOM0{slash}PAD0-Pad9)") (class "Default")
      (node (ref "U5") (pin "9") (pinfunction "PA04_/_AIN[4]_/_SERCOM0/PAD0_9") (pintype "passive"))
    )
    (net (code "93") (name "unconnected-(U5A-PA05_{slash}_AIN[5]_{slash}_SERCOM0{slash}PAD1-Pad10)") (class "Default")
      (node (ref "U5") (pin "10") (pinfunction "PA05_/_AIN[5]_/_SERCOM0/PAD1_10") (pintype "passive"))
    )
    (net (code "94") (name "unconnected-(U5A-PA06_{slash}_AIN[6]_{slash}_SERCOM0{slash}PAD2-Pad11)") (class "Default")
      (node (ref "U5") (pin "11") (pinfunction "PA06_/_AIN[6]_/_SERCOM0/PAD2_11") (pintype "passive"))
    )
    (net (code "95") (name "unconnected-(U5A-PA07_{slash}_AIN[7]_{slash}_SERCOM0{slash}PAD3-Pad12)") (class "Default")
      (node (ref "U5") (pin "12") (pinfunction "PA07_/_AIN[7]_/_SERCOM0/PAD3_12") (pintype "passive"))
    )
    (net (code "96") (name "unconnected-(U5A-PA08_{slash}_I2C_{slash}_SERCOM[0-2]{slash}PAD0-Pad13)") (class "Default")
      (node (ref "U5") (pin "13") (pinfunction "PA08_/_I2C_/_SERCOM[0-2]/PAD0_13") (pintype "passive"))
    )
    (net (code "97") (name "unconnected-(U5A-PA09_{slash}_I2C_{slash}_SERCOM[0-2]{slash}PAD1-Pad14)") (class "Default")
      (node (ref "U5") (pin "14") (pinfunction "PA09_/_I2C_/_SERCOM[0-2]/PAD1_14") (pintype "passive"))
    )
    (net (code "98") (name "unconnected-(U5A-PA10_{slash}_SERCOM[0-2]{slash}PAD2_{slash}_GCLK_IO[4]-Pad15)") (class "Default")
      (node (ref "U5") (pin "15") (pinfunction "PA10_/_SERCOM[0-2]/PAD2_/_GCLK_IO[4]_15") (pintype "passive"))
    )
    (net (code "99") (name "unconnected-(U5A-PA11_{slash}_SERCOM[0-2]{slash}PAD3_{slash}_GCLK_IO[5]-Pad16)") (class "Default")
      (node (ref "U5") (pin "16") (pinfunction "PA11_/_SERCOM[0-2]/PAD3_/_GCLK_IO[5]_16") (pintype "passive"))
    )
    (net (code "100") (name "unconnected-(U5A-PA12-Pad21)") (class "Default")
      (node (ref "U5") (pin "21") (pinfunction "PA12_21") (pintype "passive"))
    )
    (net (code "101") (name "unconnected-(U5A-PA13-Pad22)") (class "Default")
      (node (ref "U5") (pin "22") (pinfunction "PA13_22") (pintype "passive"))
    )
    (net (code "102") (name "unconnected-(U5A-PA14-Pad23)") (class "Default")
      (node (ref "U5") (pin "23") (pinfunction "PA14_23") (pintype "passive"))
    )
    (net (code "103") (name "unconnected-(U5A-PA15-Pad24)") (class "Default")
      (node (ref "U5") (pin "24") (pinfunction "PA15_24") (pintype "passive"))
    )
    (net (code "104") (name "unconnected-(U5A-PA16-Pad25)") (class "Default")
      (node (ref "U5") (pin "25") (pinfunction "PA16_25") (pintype "passive"))
    )
    (net (code "105") (name "unconnected-(U5A-PA17-Pad26)") (class "Default")
      (node (ref "U5") (pin "26") (pinfunction "PA17_26") (pintype "passive"))
    )
    (net (code "106") (name "unconnected-(U5A-PA18-Pad27)") (class "Default")
      (node (ref "U5") (pin "27") (pinfunction "PA18_27") (pintype "passive"))
    )
    (net (code "107") (name "unconnected-(U5A-PA19-Pad28)") (class "Default")
      (node (ref "U5") (pin "28") (pinfunction "PA19_28") (pintype "passive"))
    )
    (net (code "108") (name "unconnected-(U5A-PA20-Pad29)") (class "Default")
      (node (ref "U5") (pin "29") (pinfunction "PA20_29") (pintype "passive"))
    )
    (net (code "109") (name "unconnected-(U5A-PA21-Pad30)") (class "Default")
      (node (ref "U5") (pin "30") (pinfunction "PA21_30") (pintype "passive"))
    )
    (net (code "110") (name "unconnected-(U5A-PA27-Pad39)") (class "Default")
      (node (ref "U5") (pin "39") (pinfunction "PA27_39") (pintype "passive"))
    )
    (net (code "111") (name "unconnected-(U5A-PA28-Pad41)") (class "Default")
      (node (ref "U5") (pin "41") (pinfunction "PA28_41") (pintype "passive"))
    )
    (net (code "112") (name "unconnected-(U5A-PB02-Pad47)") (class "Default")
      (node (ref "U5") (pin "47") (pinfunction "PB02_47") (pintype "passive"))
    )
    (net (code "113") (name "unconnected-(U5A-PB03-Pad48)") (class "Default")
      (node (ref "U5") (pin "48") (pinfunction "PB03_48") (pintype "passive"))
    )
    (net (code "114") (name "unconnected-(U5A-PB08_{slash}_AIN[2]_{slash}_SERCOM4{slash}PAD0-Pad7)") (class "Default")
      (node (ref "U5") (pin "7") (pinfunction "PB08_/_AIN[2]_/_SERCOM4/PAD0_7") (pintype "passive"))
    )
    (net (code "115") (name "unconnected-(U5A-PB09_{slash}_AIN[3]_{slash}_SERCOM4{slash}PAD1-Pad8)") (class "Default")
      (node (ref "U5") (pin "8") (pinfunction "PB09_/_AIN[3]_/_SERCOM4/PAD1_8") (pintype "passive"))
    )
    (net (code "116") (name "unconnected-(U5A-PB10_{slash}_SERCOM4{slash}PAD2_{slash}_GCLK_IO[4]-Pad19)") (class "Default")
      (node (ref "U5") (pin "19") (pinfunction "PB10_/_SERCOM4/PAD2_/_GCLK_IO[4]_19") (pintype "passive"))
    )
    (net (code "117") (name "unconnected-(U5A-PB11_{slash}_SERCOM4{slash}PAD3_{slash}_GCLK_IO[5]-Pad20)") (class "Default")
      (node (ref "U5") (pin "20") (pinfunction "PB11_/_SERCOM4/PAD3_/_GCLK_IO[5]_20") (pintype "passive"))
    )
    (net (code "118") (name "unconnected-(U5A-PB22-Pad37)") (class "Default")
      (node (ref "U5") (pin "37") (pinfunction "PB22_37") (pintype "passive"))
    )
    (net (code "119") (name "unconnected-(U5A-PB23-Pad38)") (class "Default")
      (node (ref "U5") (pin "38") (pinfunction "PB23_38") (pintype "passive"))
    )
  )
)
